# TinyIRCam-breakout-mk-1_0.net
KiCad netlist of a schematic drawn in EAGLE
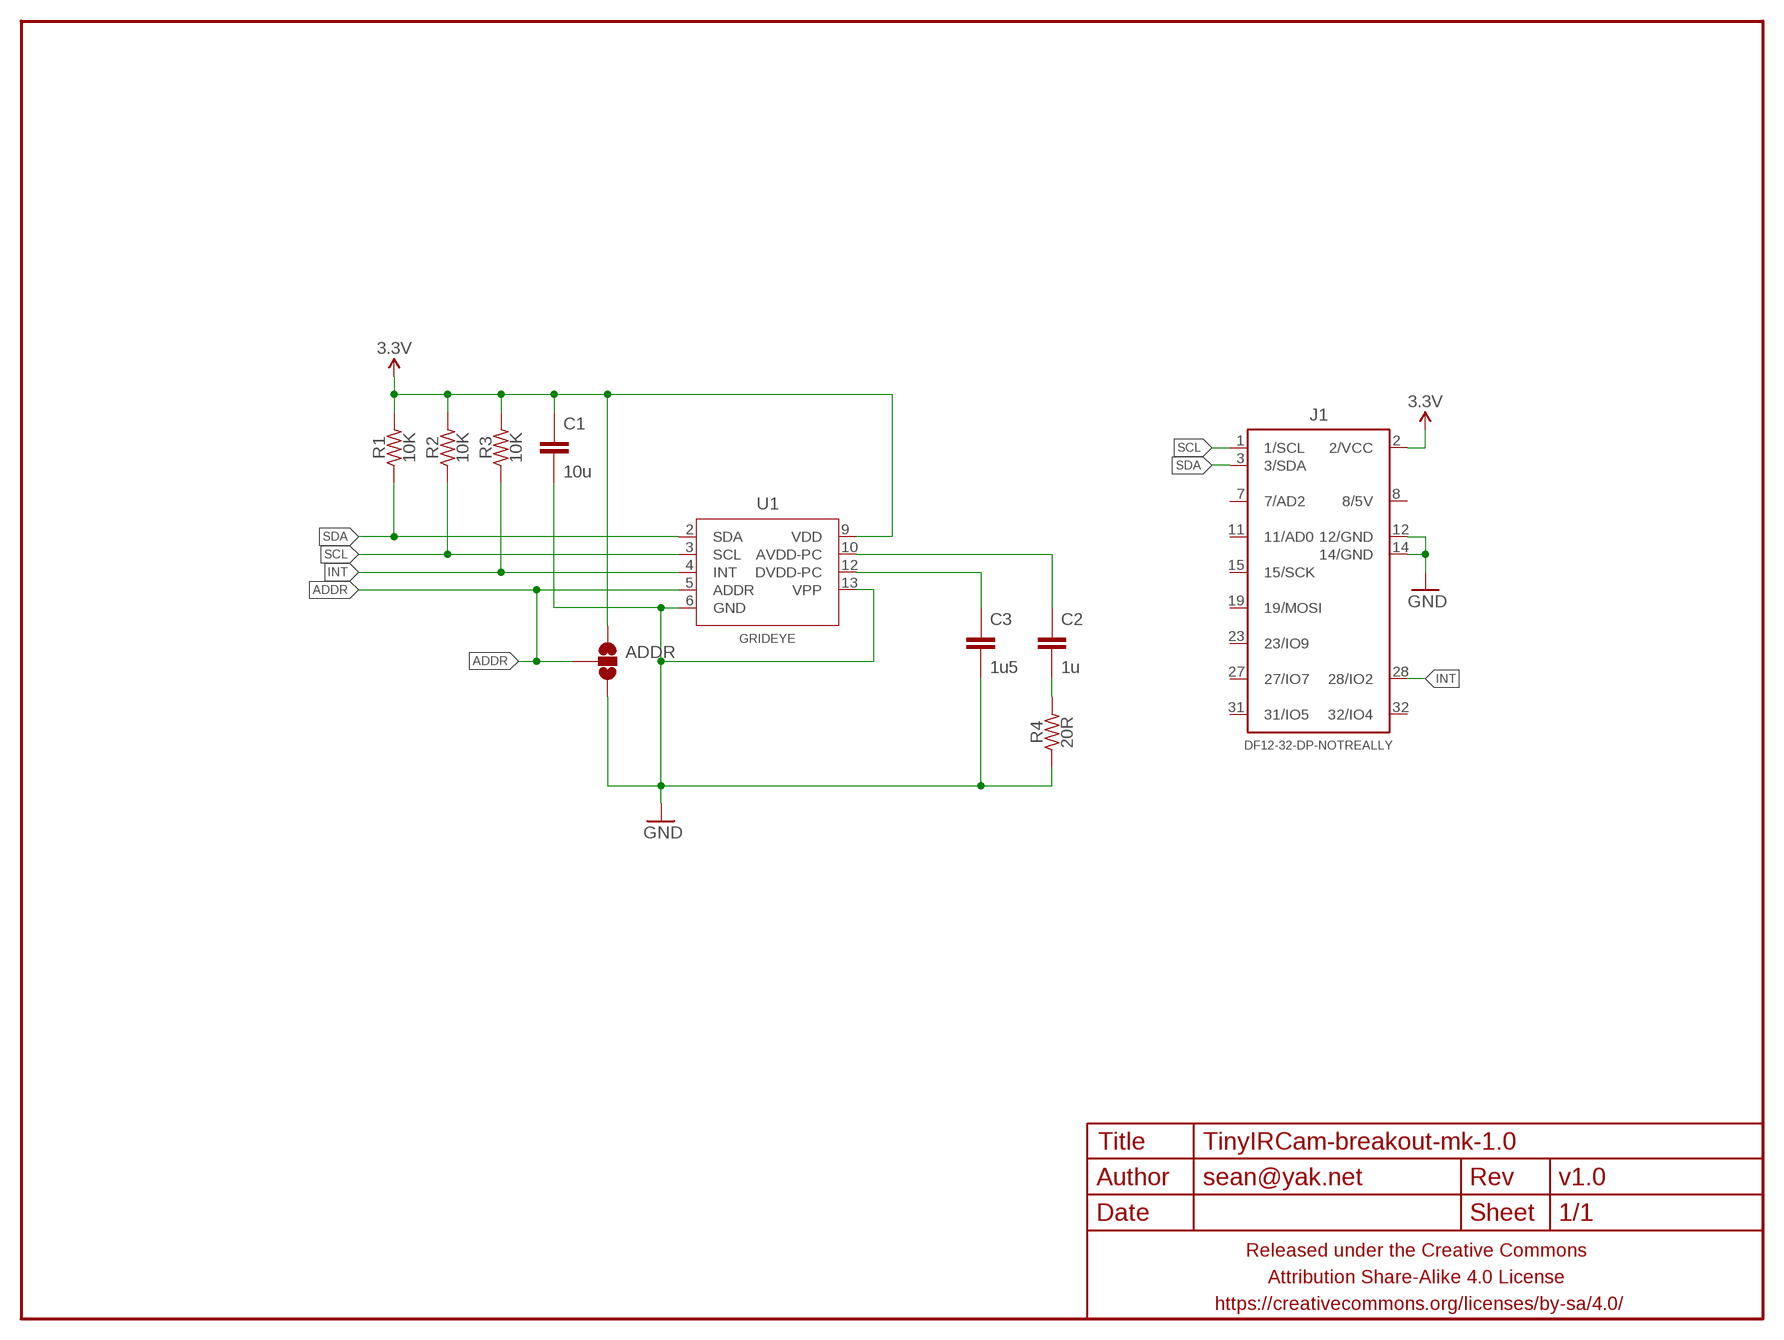
[diagram p0: schematic, sheet 1]

(export (version "E")
  (design (tool "Eeschema 10.0.6"))
  (components
    (comp (ref "ADDR")
      (value "JUMPER-PAD-3-NOSMALLER")
      (footprint "eagle-import:PAD-JUMPER-3-NO_YES_SILK_FULL_BOX_SMALLER")
      (libsource (lib "eagle-import") (part "JUMPER-PAD-3-NOSMALLER"))
    )
    (comp (ref "C1")
      (value "10u")
      (footprint "eagle-import:C0603-TIGHTER")
      (libsource (lib "eagle-import") (part "CAPACITOR-CERAMICC0603-TIGHTER"))
    )
    (comp (ref "C2")
      (value "1u")
      (footprint "eagle-import:C0603-TIGHTER")
      (libsource (lib "eagle-import") (part "CAPACITOR-CERAMICC0603-TIGHTER"))
    )
    (comp (ref "C3")
      (value "1u5")
      (footprint "eagle-import:C0603-TIGHTER")
      (libsource (lib "eagle-import") (part "CAPACITOR-CERAMICC0603-TIGHTER"))
    )
    (comp (ref "FRAME1")
      (value "FRAME-LETTERNO_PACKAGE")
      (footprint "eagle-import:DUMMY")
      (fields (field (name "DESIGNER") "sean@yak.net") (field (name "VERSION") "v1.0"))
      (libsource (lib "eagle-import") (part "FRAME-LETTERNO_PACKAGE"))
    )
    (comp (ref "J1")
      (value "DF12-32-DP-NOTREALLY")
      (footprint "eagle-import:DF12-32-DP-I2C+EXTRA")
      (libsource (lib "eagle-import") (part "DF12-32-DP-NOTREALLY"))
    )
    (comp (ref "R1")
      (value "10K")
      (footprint "eagle-import:R0603-TIGHTER")
      (libsource (lib "eagle-import") (part "RESISTORR0603-TIGHTER"))
    )
    (comp (ref "R2")
      (value "10K")
      (footprint "eagle-import:R0603-TIGHTER")
      (libsource (lib "eagle-import") (part "RESISTORR0603-TIGHTER"))
    )
    (comp (ref "R3")
      (value "10K")
      (footprint "eagle-import:R0603-TIGHTER")
      (libsource (lib "eagle-import") (part "RESISTORR0603-TIGHTER"))
    )
    (comp (ref "R4")
      (value "20R")
      (footprint "eagle-import:R0603-TIGHTER")
      (libsource (lib "eagle-import") (part "RESISTORR0603-TIGHTER"))
    )
    (comp (ref "U1")
      (value "GRIDEYE")
      (footprint "eagle-import:GRIDEYE")
      (libsource (lib "eagle-import") (part "GRIDEYE"))
    )
  )
  (nets
    (net (code "1") (name "3.3V") (class "Default")
      (node (ref "ADDR") (pin "1") (pinfunction "1_1") (pintype "passive"))
      (node (ref "C1") (pin "1") (pinfunction "1_1") (pintype "passive"))
      (node (ref "J1") (pin "2") (pinfunction "2/VCC_2") (pintype "bidirectional"))
      (node (ref "R1") (pin "2") (pinfunction "2_2") (pintype "passive"))
      (node (ref "R2") (pin "2") (pinfunction "2_2") (pintype "passive"))
      (node (ref "R3") (pin "2") (pinfunction "2_2") (pintype "passive"))
      (node (ref "U1") (pin "9") (pinfunction "VDD_9") (pintype "bidirectional"))
    )
    (net (code "2") (name "ADDR") (class "Default")
      (node (ref "ADDR") (pin "2") (pinfunction "2_2") (pintype "passive"))
      (node (ref "U1") (pin "5") (pinfunction "ADDR_5") (pintype "bidirectional"))
    )
    (net (code "3") (name "GND") (class "Default")
      (node (ref "ADDR") (pin "3") (pinfunction "3_3") (pintype "passive"))
      (node (ref "C1") (pin "2") (pinfunction "2_2") (pintype "passive"))
      (node (ref "C3") (pin "2") (pinfunction "2_2") (pintype "passive"))
      (node (ref "J1") (pin "12") (pinfunction "12/GND_12") (pintype "bidirectional"))
      (node (ref "J1") (pin "14") (pinfunction "14/GND_14") (pintype "bidirectional"))
      (node (ref "R4") (pin "1") (pinfunction "1_1") (pintype "passive"))
      (node (ref "U1") (pin "13") (pinfunction "VPP_13") (pintype "bidirectional"))
      (node (ref "U1") (pin "6") (pinfunction "GND_6") (pintype "bidirectional"))
    )
    (net (code "4") (name "INT") (class "Default")
      (node (ref "J1") (pin "28") (pinfunction "28/IO2_28") (pintype "bidirectional"))
      (node (ref "R3") (pin "1") (pinfunction "1_1") (pintype "passive"))
      (node (ref "U1") (pin "4") (pinfunction "INT_4") (pintype "bidirectional"))
    )
    (net (code "5") (name "Net-(C2-Pad2)") (class "Default")
      (node (ref "C2") (pin "2") (pinfunction "2_2") (pintype "passive"))
      (node (ref "R4") (pin "2") (pinfunction "2_2") (pintype "passive"))
    )
    (net (code "6") (name "Net-(U1-AVDD-PC)") (class "Default")
      (node (ref "C2") (pin "1") (pinfunction "1_1") (pintype "passive"))
      (node (ref "U1") (pin "10") (pinfunction "AVDD-PC_10") (pintype "bidirectional"))
    )
    (net (code "7") (name "Net-(U1-DVDD-PC)") (class "Default")
      (node (ref "C3") (pin "1") (pinfunction "1_1") (pintype "passive"))
      (node (ref "U1") (pin "12") (pinfunction "DVDD-PC_12") (pintype "bidirectional"))
    )
    (net (code "8") (name "SCL") (class "Default")
      (node (ref "J1") (pin "1") (pinfunction "1/SCL_1") (pintype "bidirectional"))
      (node (ref "R2") (pin "1") (pinfunction "1_1") (pintype "passive"))
      (node (ref "U1") (pin "3") (pinfunction "SCL_3") (pintype "bidirectional"))
    )
    (net (code "9") (name "SDA") (class "Default")
      (node (ref "J1") (pin "3") (pinfunction "3/SDA_3") (pintype "bidirectional"))
      (node (ref "R1") (pin "1") (pinfunction "1_1") (pintype "passive"))
      (node (ref "U1") (pin "2") (pinfunction "SDA_2") (pintype "bidirectional"))
    )
    (net (code "10") (name "unconnected-(J1-7{slash}AD2-Pad7)") (class "Default")
      (node (ref "J1") (pin "7") (pinfunction "7/AD2_7") (pintype "bidirectional"))
    )
    (net (code "11") (name "unconnected-(J1-8{slash}5V-Pad8)") (class "Default")
      (node (ref "J1") (pin "8") (pinfunction "8/5V_8") (pintype "bidirectional"))
    )
    (net (code "12") (name "unconnected-(J1-11{slash}AD0-Pad11)") (class "Default")
      (node (ref "J1") (pin "11") (pinfunction "11/AD0_11") (pintype "bidirectional"))
    )
    (net (code "13") (name "unconnected-(J1-15{slash}SCK-Pad15)") (class "Default")
      (node (ref "J1") (pin "15") (pinfunction "15/SCK_15") (pintype "bidirectional"))
    )
    (net (code "14") (name "unconnected-(J1-19{slash}MOSI-Pad19)") (class "Default")
      (node (ref "J1") (pin "19") (pinfunction "19/MOSI_19") (pintype "bidirectional"))
    )
    (net (code "15") (name "unconnected-(J1-23{slash}IO9-Pad23)") (class "Default")
      (node (ref "J1") (pin "23") (pinfunction "23/IO9_23") (pintype "bidirectional"))
    )
    (net (code "16") (name "unconnected-(J1-27{slash}IO7-Pad27)") (class "Default")
      (node (ref "J1") (pin "27") (pinfunction "27/IO7_27") (pintype "bidirectional"))
    )
    (net (code "17") (name "unconnected-(J1-31{slash}IO5-Pad31)") (class "Default")
      (node (ref "J1") (pin "31") (pinfunction "31/IO5_31") (pintype "bidirectional"))
    )
    (net (code "18") (name "unconnected-(J1-32{slash}IO4-Pad32)") (class "Default")
      (node (ref "J1") (pin "32") (pinfunction "32/IO4_32") (pintype "bidirectional"))
    )
  )
)
